# design.net
KiCad netlist of a schematic drawn in Altium Designer
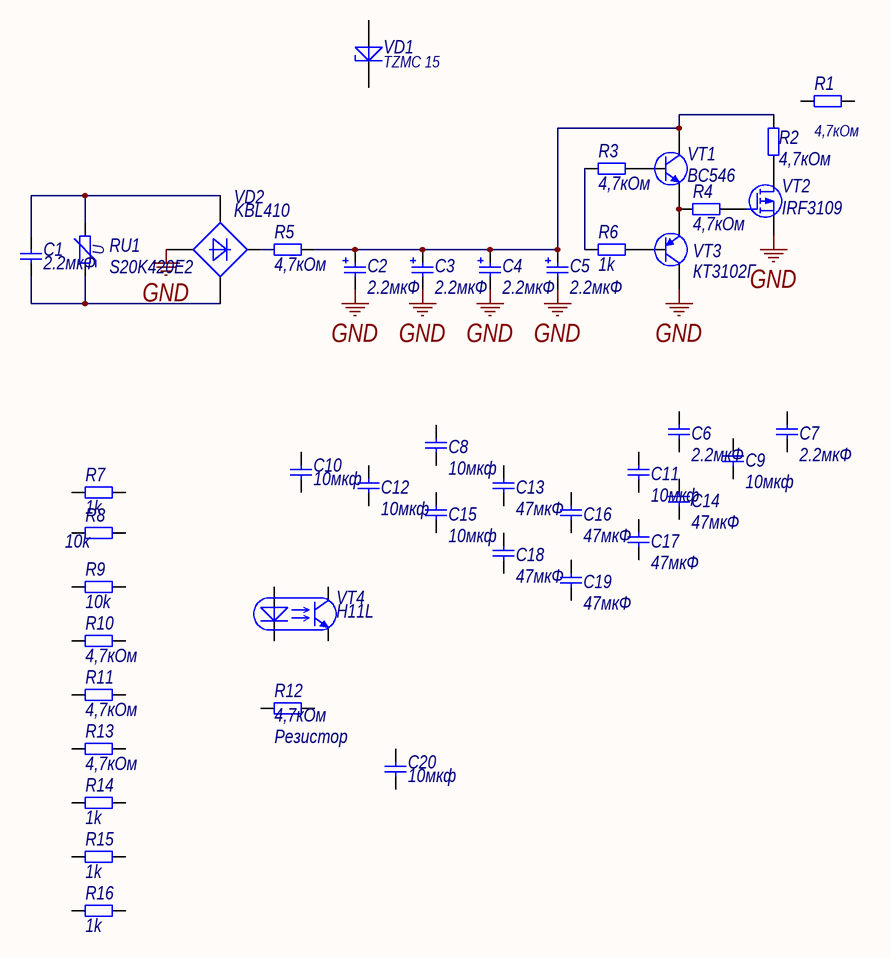
[diagram p0: пример схемы с элементами.SchDoc]

(export (version "E")
  (design (tool "Eeschema 10.0.6"))
  (components
    (comp (ref "C1")
      (value "2.2мкФ")
      (description "Конденсатор непол рный")
      (fields (field (name "MANUFACTURER") "Murata") (field (name "TOLERANCE") "10%"))
      (libsource (lib "Schlibgost2") (part "C nonpol"))
    )
    (comp (ref "C2")
      (value "2.2мкФ")
      (description "Конденсатор пол рный")
      (fields (field (name "MANUFACTURER") "Murata") (field (name "TOLERANCE") "10%"))
      (libsource (lib "Schlibgost2") (part "C pol"))
    )
    (comp (ref "C3")
      (value "2.2мкФ")
      (description "Конденсатор пол рный")
      (fields (field (name "MANUFACTURER") "Murata") (field (name "TOLERANCE") "10%"))
      (libsource (lib "Schlibgost2") (part "C pol"))
    )
    (comp (ref "C4")
      (value "2.2мкФ")
      (description "Конденсатор пол рный")
      (fields (field (name "MANUFACTURER") "Murata") (field (name "TOLERANCE") "10%"))
      (libsource (lib "Schlibgost2") (part "C pol"))
    )
    (comp (ref "C5")
      (value "2.2мкФ")
      (description "Конденсатор пол рный")
      (fields (field (name "MANUFACTURER") "Murata") (field (name "TOLERANCE") "10%"))
      (libsource (lib "Schlibgost2") (part "C pol"))
    )
    (comp (ref "C6")
      (value "2.2мкФ")
      (description "Конденсатор непол рный")
      (fields (field (name "MANUFACTURER") "Murata") (field (name "TOLERANCE") "10%"))
      (libsource (lib "Schlibgost2") (part "C nonpol"))
    )
    (comp (ref "C7")
      (value "2.2мкФ")
      (description "Конденсатор непол рный")
      (fields (field (name "MANUFACTURER") "Murata") (field (name "TOLERANCE") "10%"))
      (libsource (lib "Schlibgost2") (part "C nonpol"))
    )
    (comp (ref "C8")
      (value "10мкф")
      (description "Конденсатор непол рный")
      (fields
        (field (name "MANUFACTURER") "Hitano")
        (field (name "MANUFACTURERPARTNUMBER") "ELV10106FKS2112")
      )
      (libsource (lib "Schlibgost2") (part "C nonpol"))
    )
    (comp (ref "C9")
      (value "10мкф")
      (description "Конденсатор непол рный")
      (fields
        (field (name "MANUFACTURER") "Hitano")
        (field (name "MANUFACTURERPARTNUMBER") "ELV10106FKS2112")
      )
      (libsource (lib "Schlibgost2") (part "C nonpol"))
    )
    (comp (ref "C10")
      (value "10мкф")
      (description "Конденсатор непол рный")
      (fields
        (field (name "MANUFACTURER") "Hitano")
        (field (name "MANUFACTURERPARTNUMBER") "ELV10106FKS2112")
      )
      (libsource (lib "Schlibgost2") (part "C nonpol"))
    )
    (comp (ref "C11")
      (value "10мкф")
      (description "Конденсатор непол рный")
      (fields
        (field (name "MANUFACTURER") "Hitano")
        (field (name "MANUFACTURERPARTNUMBER") "ELV10106FKS2112")
      )
      (libsource (lib "Schlibgost2") (part "C nonpol"))
    )
    (comp (ref "C12")
      (value "10мкф")
      (description "Конденсатор непол рный")
      (fields
        (field (name "MANUFACTURER") "Hitano")
        (field (name "MANUFACTURERPARTNUMBER") "ELV10106FKS2112")
      )
      (libsource (lib "Schlibgost2") (part "C nonpol"))
    )
    (comp (ref "C13")
      (value "47мкФ")
      (description "Конденсатор непол рный")
      (fields (field (name "TOLERANCE") "+/-10%"))
      (libsource (lib "Schlibgost2") (part "C nonpol"))
    )
    (comp (ref "C14")
      (value "47мкФ")
      (description "Конденсатор непол рный")
      (fields (field (name "TOLERANCE") "+/-10%"))
      (libsource (lib "Schlibgost2") (part "C nonpol"))
    )
    (comp (ref "C15")
      (value "10мкф")
      (description "Конденсатор непол рный")
      (fields
        (field (name "MANUFACTURER") "Hitano")
        (field (name "MANUFACTURERPARTNUMBER") "ELV10106FKS2112")
      )
      (libsource (lib "Schlibgost2") (part "C nonpol"))
    )
    (comp (ref "C16")
      (value "47мкФ")
      (description "Конденсатор непол рный")
      (fields (field (name "TOLERANCE") "+/-10%"))
      (libsource (lib "Schlibgost2") (part "C nonpol"))
    )
    (comp (ref "C17")
      (value "47мкФ")
      (description "Конденсатор непол рный")
      (fields (field (name "TOLERANCE") "+/-10%"))
      (libsource (lib "Schlibgost2") (part "C nonpol"))
    )
    (comp (ref "C18")
      (value "47мкФ")
      (description "Конденсатор непол рный")
      (fields (field (name "TOLERANCE") "+/-10%"))
      (libsource (lib "Schlibgost2") (part "C nonpol"))
    )
    (comp (ref "C19")
      (value "47мкФ")
      (description "Конденсатор непол рный")
      (fields (field (name "TOLERANCE") "+/-10%"))
      (libsource (lib "Schlibgost2") (part "C nonpol"))
    )
    (comp (ref "C20")
      (value "10мкф")
      (description "Конденсатор непол рный")
      (fields
        (field (name "MANUFACTURER") "Hitano")
        (field (name "MANUFACTURERPARTNUMBER") "ELV10106FKS2112")
      )
      (libsource (lib "Schlibgost2") (part "C nonpol"))
    )
    (comp (ref "R1")
      (value "4,7кОм")
      (description "Резистор")
      (fields (field (name "TOLERANCE") "+/-5%"))
      (libsource (lib "Schlibgost2") (part "R"))
    )
    (comp (ref "R2")
      (value "4,7кОм")
      (description "Резистор")
      (fields (field (name "TOLERANCE") "+/-5%"))
      (libsource (lib "") (part "R_1"))
    )
    (comp (ref "R3")
      (value "4,7кОм")
      (description "Резистор")
      (fields (field (name "TOLERANCE") "+/-5%"))
      (libsource (lib "Schlibgost2") (part "R"))
    )
    (comp (ref "R4")
      (value "4,7кОм")
      (description "Резистор")
      (fields (field (name "TOLERANCE") "+/-5%"))
      (libsource (lib "Schlibgost2") (part "R"))
    )
    (comp (ref "R5")
      (value "4,7кОм")
      (description "Резистор")
      (fields (field (name "TOLERANCE") "+/-5%"))
      (libsource (lib "Schlibgost2") (part "R"))
    )
    (comp (ref "R6")
      (value "1k")
      (description "Резистор")
      (fields (field (name "TOLERANCE") "0.1%"))
      (libsource (lib "Schlibgost2") (part "R"))
    )
    (comp (ref "R7")
      (value "1k")
      (description "Резистор")
      (fields (field (name "TOLERANCE") "0.1%"))
      (libsource (lib "Schlibgost2") (part "R"))
    )
    (comp (ref "R8")
      (value "10k")
      (description "Резистор")
      (fields (field (name "TOLERANCE") "0.1%") (field (name "MANUFACTURER") "Yageo"))
      (libsource (lib "Schlibgost2") (part "R"))
    )
    (comp (ref "R9")
      (value "10k")
      (description "Резистор")
      (fields (field (name "MANUFACTURER") "Yageo") (field (name "MANUFACTURERPARTNUMBER") "1206R103BLABLA"))
      (libsource (lib "Schlibgost2") (part "R"))
    )
    (comp (ref "R10")
      (value "4,7кОм")
      (description "Резистор")
      (fields (field (name "TOLERANCE") "+/-5%"))
      (libsource (lib "Schlibgost2") (part "R"))
    )
    (comp (ref "R11")
      (value "4,7кОм")
      (description "Резистор")
      (fields (field (name "MANUFACTURERPARTNUMBER") "Р1-12 - 0,125ФИ - 4,7кОм +/-5% - М"))
      (libsource (lib "Schlibgost2") (part "R"))
    )
    (comp (ref "R12")
      (value "4,7кОм")
      (description "Резистор")
      (fields (field (name "TOLERANCE") "+/-5%") (field (name "TYPE") "Резистор"))
      (libsource (lib "Schlibgost2") (part "R"))
    )
    (comp (ref "R13")
      (value "4,7кОм")
      (description "Резистор")
      (fields (field (name "TOLERANCE") "+/-5%"))
      (libsource (lib "Schlibgost2") (part "R"))
    )
    (comp (ref "R14")
      (value "1k")
      (description "Резистор")
      (fields (field (name "TOLERANCE") "0.1%"))
      (libsource (lib "Schlibgost2") (part "R"))
    )
    (comp (ref "R15")
      (value "1k")
      (description "Резистор")
      (fields (field (name "TOLERANCE") "0.1%"))
      (libsource (lib "Schlibgost2") (part "R"))
    )
    (comp (ref "R16")
      (value "1k")
      (description "Резистор")
      (fields (field (name "TOLERANCE") "0.1%"))
      (libsource (lib "Schlibgost2") (part "R"))
    )
    (comp (ref "RU1")
      (value "S20K420E2")
      (description "Варистор")
      (fields (field (name "MANUFACTURER") "Epcos") (field (name "MANUFACTURERPARTNUMBER") "S20K420E2"))
      (libsource (lib "Schlibgost2") (part "RU Varistor"))
    )
    (comp (ref "VD1")
      (value "TZMC 15")
      (description "Стабилитрон односторонний")
      (fields (field (name "MANUFACTURER") "Vishay"))
      (libsource (lib "Schlibgost2") (part "VD Stabilitron"))
    )
    (comp (ref "VD2")
      (value "KBL410")
      (description "Диодный мост")
      (fields (field (name "MANUFACTURERPARTNUMBER") "KBL410"))
      (libsource (lib "Schlibgost2") (part "VD Bridge diod"))
    )
    (comp (ref "VT1")
      (value "BC546")
      (description "Транзистор бипол рный n-p-n")
      (fields (field (name "MANUFACTURER") "Vishay") (field (name "MANUFACTURERPARTNUMBER") "BC546"))
      (libsource (lib "Schlibgost2") (part "VT Transistor NPN"))
    )
    (comp (ref "VT2")
      (value "IRF3109")
      (description "Транзистор полевой p-канальный")
      (fields (field (name "MANUFACTURER") "IRF") (field (name "MANUFACTURERPARTNUMBER") "IRF3109"))
      (libsource (lib "Schlibgost2") (part "VT Transistor PMOS"))
    )
    (comp (ref "VT3")
      (value "КТ3102Г")
      (description "Транзистор бипол рный p-n-p")
      (fields (field (name "MANUFACTURERPARTNUMBER") "КТ3102Г"))
      (libsource (lib "Schlibgost2") (part "VT Transistor PNP"))
    )
    (comp (ref "VT4")
      (value "H11L")
      (description "Оптрон транзисторный")
      (fields (field (name "MANUFACTURER") "BurrBrown"))
      (libsource (lib "Schlibgost2") (part "Optron1"))
    )
  )
  (nets
    (net (code "1") (name "GND") (class "Default")
      (node (ref "C2") (pin "2") (pinfunction "2_2") (pintype "passive"))
      (node (ref "C3") (pin "2") (pinfunction "2_2") (pintype "passive"))
      (node (ref "C4") (pin "2") (pinfunction "2_2") (pintype "passive"))
      (node (ref "C5") (pin "2") (pinfunction "2_2") (pintype "passive"))
      (node (ref "VD2") (pin "1") (pinfunction "A_1") (pintype "passive"))
      (node (ref "VT2") (pin "3") (pinfunction "S_3") (pintype "passive"))
      (node (ref "VT3") (pin "3") (pinfunction "C_3") (pintype "passive"))
    )
    (net (code "2") (name "Net-(C1-Pad1)") (class "Default")
      (node (ref "C1") (pin "1") (pinfunction "1_1") (pintype "passive"))
      (node (ref "RU1") (pin "2") (pinfunction "2_2") (pintype "passive"))
      (node (ref "VD2") (pin "2") (pinfunction "C_2") (pintype "passive"))
    )
    (net (code "3") (name "Net-(C1-Pad2)") (class "Default")
      (node (ref "C1") (pin "2") (pinfunction "2_2") (pintype "passive"))
      (node (ref "RU1") (pin "1") (pinfunction "1_1") (pintype "passive"))
      (node (ref "VD2") (pin "4") (pinfunction "C_4") (pintype "passive"))
    )
    (net (code "4") (name "Net-(R3-Pad1)") (class "Default")
      (node (ref "R3") (pin "1") (pinfunction "1_1") (pintype "passive"))
      (node (ref "R6") (pin "1") (pinfunction "1_1") (pintype "passive"))
    )
    (net (code "5") (name "Net-(VD2-K)") (class "Default")
      (node (ref "R5") (pin "1") (pinfunction "1_1") (pintype "passive"))
      (node (ref "VD2") (pin "3") (pinfunction "K_3") (pintype "passive"))
    )
    (net (code "6") (name "Net-(VT1-B)") (class "Default")
      (node (ref "R3") (pin "2") (pinfunction "2_2") (pintype "passive"))
      (node (ref "VT1") (pin "2") (pinfunction "B_2") (pintype "passive"))
    )
    (net (code "7") (name "Net-(VT1-C)") (class "Default")
      (node (ref "C2") (pin "1") (pinfunction "1_1") (pintype "passive"))
      (node (ref "C3") (pin "1") (pinfunction "1_1") (pintype "passive"))
      (node (ref "C4") (pin "1") (pinfunction "1_1") (pintype "passive"))
      (node (ref "C5") (pin "1") (pinfunction "1_1") (pintype "passive"))
      (node (ref "R2") (pin "2") (pinfunction "2_2") (pintype "passive"))
      (node (ref "R5") (pin "2") (pinfunction "2_2") (pintype "passive"))
      (node (ref "VT1") (pin "1") (pinfunction "C_1") (pintype "passive"))
    )
    (net (code "8") (name "Net-(VT1-E)") (class "Default")
      (node (ref "R4") (pin "1") (pinfunction "1_1") (pintype "passive"))
      (node (ref "VT1") (pin "3") (pinfunction "E_3") (pintype "passive"))
      (node (ref "VT3") (pin "1") (pinfunction "E_1") (pintype "passive"))
    )
    (net (code "9") (name "Net-(VT2-D)") (class "Default")
      (node (ref "R2") (pin "1") (pinfunction "1_1") (pintype "passive"))
      (node (ref "VT2") (pin "1") (pinfunction "D_1") (pintype "passive"))
    )
    (net (code "10") (name "Net-(VT2-G)") (class "Default")
      (node (ref "R4") (pin "2") (pinfunction "2_2") (pintype "passive"))
      (node (ref "VT2") (pin "2") (pinfunction "G_2") (pintype "passive"))
    )
    (net (code "11") (name "Net-(VT3-B)") (class "Default")
      (node (ref "R6") (pin "2") (pinfunction "2_2") (pintype "passive"))
      (node (ref "VT3") (pin "2") (pinfunction "B_2") (pintype "passive"))
    )
    (net (code "12") (name "unconnected-(C6-Pad1)") (class "Default")
      (node (ref "C6") (pin "1") (pinfunction "1_1") (pintype "passive"))
    )
    (net (code "13") (name "unconnected-(C6-Pad2)") (class "Default")
      (node (ref "C6") (pin "2") (pinfunction "2_2") (pintype "passive"))
    )
    (net (code "14") (name "unconnected-(C7-Pad1)") (class "Default")
      (node (ref "C7") (pin "1") (pinfunction "1_1") (pintype "passive"))
    )
    (net (code "15") (name "unconnected-(C7-Pad2)") (class "Default")
      (node (ref "C7") (pin "2") (pinfunction "2_2") (pintype "passive"))
    )
    (net (code "16") (name "unconnected-(C8-Pad1)") (class "Default")
      (node (ref "C8") (pin "1") (pinfunction "1_1") (pintype "passive"))
    )
    (net (code "17") (name "unconnected-(C8-Pad2)") (class "Default")
      (node (ref "C8") (pin "2") (pinfunction "2_2") (pintype "passive"))
    )
    (net (code "18") (name "unconnected-(C9-Pad1)") (class "Default")
      (node (ref "C9") (pin "1") (pinfunction "1_1") (pintype "passive"))
    )
    (net (code "19") (name "unconnected-(C9-Pad2)") (class "Default")
      (node (ref "C9") (pin "2") (pinfunction "2_2") (pintype "passive"))
    )
    (net (code "20") (name "unconnected-(C10-Pad1)") (class "Default")
      (node (ref "C10") (pin "1") (pinfunction "1_1") (pintype "passive"))
    )
    (net (code "21") (name "unconnected-(C10-Pad2)") (class "Default")
      (node (ref "C10") (pin "2") (pinfunction "2_2") (pintype "passive"))
    )
    (net (code "22") (name "unconnected-(C11-Pad1)") (class "Default")
      (node (ref "C11") (pin "1") (pinfunction "1_1") (pintype "passive"))
    )
    (net (code "23") (name "unconnected-(C11-Pad2)") (class "Default")
      (node (ref "C11") (pin "2") (pinfunction "2_2") (pintype "passive"))
    )
    (net (code "24") (name "unconnected-(C12-Pad1)") (class "Default")
      (node (ref "C12") (pin "1") (pinfunction "1_1") (pintype "passive"))
    )
    (net (code "25") (name "unconnected-(C12-Pad2)") (class "Default")
      (node (ref "C12") (pin "2") (pinfunction "2_2") (pintype "passive"))
    )
    (net (code "26") (name "unconnected-(C13-Pad1)") (class "Default")
      (node (ref "C13") (pin "1") (pinfunction "1_1") (pintype "passive"))
    )
    (net (code "27") (name "unconnected-(C13-Pad2)") (class "Default")
      (node (ref "C13") (pin "2") (pinfunction "2_2") (pintype "passive"))
    )
    (net (code "28") (name "unconnected-(C14-Pad1)") (class "Default")
      (node (ref "C14") (pin "1") (pinfunction "1_1") (pintype "passive"))
    )
    (net (code "29") (name "unconnected-(C14-Pad2)") (class "Default")
      (node (ref "C14") (pin "2") (pinfunction "2_2") (pintype "passive"))
    )
    (net (code "30") (name "unconnected-(C15-Pad1)") (class "Default")
      (node (ref "C15") (pin "1") (pinfunction "1_1") (pintype "passive"))
    )
    (net (code "31") (name "unconnected-(C15-Pad2)") (class "Default")
      (node (ref "C15") (pin "2") (pinfunction "2_2") (pintype "passive"))
    )
    (net (code "32") (name "unconnected-(C16-Pad1)") (class "Default")
      (node (ref "C16") (pin "1") (pinfunction "1_1") (pintype "passive"))
    )
    (net (code "33") (name "unconnected-(C16-Pad2)") (class "Default")
      (node (ref "C16") (pin "2") (pinfunction "2_2") (pintype "passive"))
    )
    (net (code "34") (name "unconnected-(C17-Pad1)") (class "Default")
      (node (ref "C17") (pin "1") (pinfunction "1_1") (pintype "passive"))
    )
    (net (code "35") (name "unconnected-(C17-Pad2)") (class "Default")
      (node (ref "C17") (pin "2") (pinfunction "2_2") (pintype "passive"))
    )
    (net (code "36") (name "unconnected-(C18-Pad1)") (class "Default")
      (node (ref "C18") (pin "1") (pinfunction "1_1") (pintype "passive"))
    )
    (net (code "37") (name "unconnected-(C18-Pad2)") (class "Default")
      (node (ref "C18") (pin "2") (pinfunction "2_2") (pintype "passive"))
    )
    (net (code "38") (name "unconnected-(C19-Pad1)") (class "Default")
      (node (ref "C19") (pin "1") (pinfunction "1_1") (pintype "passive"))
    )
    (net (code "39") (name "unconnected-(C19-Pad2)") (class "Default")
      (node (ref "C19") (pin "2") (pinfunction "2_2") (pintype "passive"))
    )
    (net (code "40") (name "unconnected-(C20-Pad1)") (class "Default")
      (node (ref "C20") (pin "1") (pinfunction "1_1") (pintype "passive"))
    )
    (net (code "41") (name "unconnected-(C20-Pad2)") (class "Default")
      (node (ref "C20") (pin "2") (pinfunction "2_2") (pintype "passive"))
    )
    (net (code "42") (name "unconnected-(R1-Pad1)") (class "Default")
      (node (ref "R1") (pin "1") (pinfunction "1_1") (pintype "passive"))
    )
    (net (code "43") (name "unconnected-(R1-Pad2)") (class "Default")
      (node (ref "R1") (pin "2") (pinfunction "2_2") (pintype "passive"))
    )
    (net (code "44") (name "unconnected-(R7-Pad1)") (class "Default")
      (node (ref "R7") (pin "1") (pinfunction "1_1") (pintype "passive"))
    )
    (net (code "45") (name "unconnected-(R7-Pad2)") (class "Default")
      (node (ref "R7") (pin "2") (pinfunction "2_2") (pintype "passive"))
    )
    (net (code "46") (name "unconnected-(R8-Pad1)") (class "Default")
      (node (ref "R8") (pin "1") (pinfunction "1_1") (pintype "passive"))
    )
    (net (code "47") (name "unconnected-(R8-Pad2)") (class "Default")
      (node (ref "R8") (pin "2") (pinfunction "2_2") (pintype "passive"))
    )
    (net (code "48") (name "unconnected-(R9-Pad1)") (class "Default")
      (node (ref "R9") (pin "1") (pinfunction "1_1") (pintype "passive"))
    )
    (net (code "49") (name "unconnected-(R9-Pad2)") (class "Default")
      (node (ref "R9") (pin "2") (pinfunction "2_2") (pintype "passive"))
    )
    (net (code "50") (name "unconnected-(R10-Pad1)") (class "Default")
      (node (ref "R10") (pin "1") (pinfunction "1_1") (pintype "passive"))
    )
    (net (code "51") (name "unconnected-(R10-Pad2)") (class "Default")
      (node (ref "R10") (pin "2") (pinfunction "2_2") (pintype "passive"))
    )
    (net (code "52") (name "unconnected-(R11-Pad1)") (class "Default")
      (node (ref "R11") (pin "1") (pinfunction "1_1") (pintype "passive"))
    )
    (net (code "53") (name "unconnected-(R11-Pad2)") (class "Default")
      (node (ref "R11") (pin "2") (pinfunction "2_2") (pintype "passive"))
    )
    (net (code "54") (name "unconnected-(R12-Pad1)") (class "Default")
      (node (ref "R12") (pin "1") (pinfunction "1_1") (pintype "passive"))
    )
    (net (code "55") (name "unconnected-(R12-Pad2)") (class "Default")
      (node (ref "R12") (pin "2") (pinfunction "2_2") (pintype "passive"))
    )
    (net (code "56") (name "unconnected-(R13-Pad1)") (class "Default")
      (node (ref "R13") (pin "1") (pinfunction "1_1") (pintype "passive"))
    )
    (net (code "57") (name "unconnected-(R13-Pad2)") (class "Default")
      (node (ref "R13") (pin "2") (pinfunction "2_2") (pintype "passive"))
    )
    (net (code "58") (name "unconnected-(R14-Pad1)") (class "Default")
      (node (ref "R14") (pin "1") (pinfunction "1_1") (pintype "passive"))
    )
    (net (code "59") (name "unconnected-(R14-Pad2)") (class "Default")
      (node (ref "R14") (pin "2") (pinfunction "2_2") (pintype "passive"))
    )
    (net (code "60") (name "unconnected-(R15-Pad1)") (class "Default")
      (node (ref "R15") (pin "1") (pinfunction "1_1") (pintype "passive"))
    )
    (net (code "61") (name "unconnected-(R15-Pad2)") (class "Default")
      (node (ref "R15") (pin "2") (pinfunction "2_2") (pintype "passive"))
    )
    (net (code "62") (name "unconnected-(R16-Pad1)") (class "Default")
      (node (ref "R16") (pin "1") (pinfunction "1_1") (pintype "passive"))
    )
    (net (code "63") (name "unconnected-(R16-Pad2)") (class "Default")
      (node (ref "R16") (pin "2") (pinfunction "2_2") (pintype "passive"))
    )
    (net (code "64") (name "unconnected-(VD1-A-Pad1)") (class "Default")
      (node (ref "VD1") (pin "1") (pinfunction "A_1") (pintype "passive"))
    )
    (net (code "65") (name "unconnected-(VD1-K-Pad2)") (class "Default")
      (node (ref "VD1") (pin "2") (pinfunction "K_2") (pintype "passive"))
    )
    (net (code "66") (name "unconnected-(VT4-A-Pad1)") (class "Default")
      (node (ref "VT4") (pin "1") (pinfunction "A_1") (pintype "passive"))
    )
    (net (code "67") (name "unconnected-(VT4-C-Pad3)") (class "Default")
      (node (ref "VT4") (pin "3") (pinfunction "C_3") (pintype "passive"))
    )
    (net (code "68") (name "unconnected-(VT4-E-Pad4)") (class "Default")
      (node (ref "VT4") (pin "4") (pinfunction "E_4") (pintype "passive"))
    )
    (net (code "69") (name "unconnected-(VT4-K-Pad2)") (class "Default")
      (node (ref "VT4") (pin "2") (pinfunction "K_2") (pintype "passive"))
    )
  )
)
